# DISCRETE_OUT.net
KiCad netlist of a schematic drawn in Altium Designer
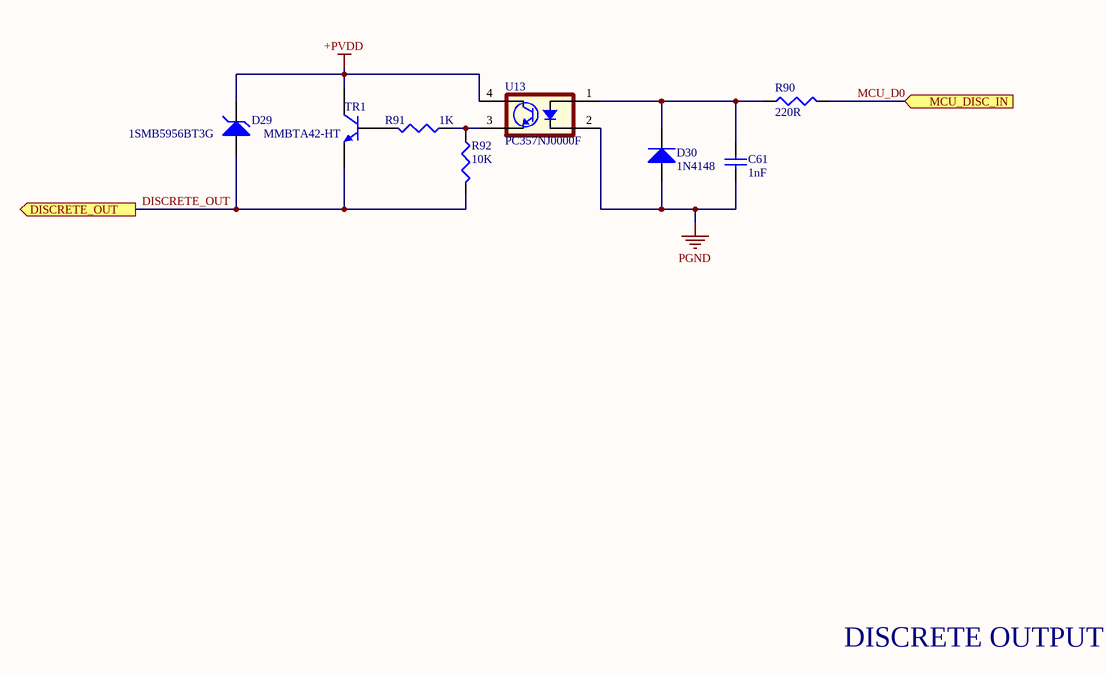
[diagram p0: DISCRETE_OUT.SchDoc]

(export (version "E")
  (design (tool "Eeschema 10.0.6"))
  (components
    (comp (ref "C61")
      (value "1nF")
      (footprint "C 0603(1608)x0.8_3")
      (description "Cap Ceramic 0.001uF 50V X7R 10% SMD 0603 125C Paper T/R")
      (fields
        (field (name "MANUFACTURER") "Murata")
        (field (name "MANUFACTURER PART NUMBER") "GCM188R71H102KA37D")
      )
      (libsource (lib "Miscellaneous Devices") (part "Cap"))
    )
    (comp (ref "D29")
      (value "1SMB5956BT3G")
      (footprint "DO214AA")
      (description "DIODE 1SMB5956BT3G ZENER 200V 3W DO214AA")
      (fields (field (name "MANUFACTURER") "ON SEMI"))
      (libsource (lib "DISCRETE_LIB") (part "DIODE 1SMB5956BT3G ZENER 200V 3W DO214AA"))
    )
    (comp (ref "D30")
      (value "1N4148")
      (footprint "SOD123")
      (description "DIODE 1N4148 GEN PURP 100V 150MA SOD123")
      (fields (field (name "MANUFACTURER") "MICRO COMMERCIAL"))
      (libsource (lib "DISCRETE_LIB") (part "DIODE 1N4148 GEN PURP 100V 150MA SOD123"))
    )
    (comp (ref "R90")
      (value "220R")
      (footprint "R 0603(1608)")
      (fields
        (field (name "MANUFACTURER") "Yageo")
        (field (name "MANUFACTURER PART NUMBER") "RC0603FR-07220RL")
        (field (name "TOLERANCE") "1%")
      )
      (libsource (lib "Miscellaneous Devices") (part "Res3"))
    )
    (comp (ref "R91")
      (value "1K")
      (footprint "R 0603(1608)")
      (description "RES SMD 1K OHM 1% 1/10W 0603")
      (fields
        (field (name "MANUFACTURER") "Yageo")
        (field (name "MANUFACTURER PART NUMBER") "RC0603FR-071KL")
      )
      (libsource (lib "Miscellaneous Devices") (part "Res3"))
    )
    (comp (ref "R92")
      (value "10K")
      (footprint "R 0603(1608)")
      (description "Res General Purpose Thick Film 0603 10K Ohm 1% 1/10W ±100ppm/°C Molded SMD Paper T/R")
      (fields
        (field (name "MANUFACTURER") "Yageo")
        (field (name "MANUFACTURER PART NUMBER") "RC0603FR-0710KL")
      )
      (libsource (lib "Miscellaneous Devices") (part "Res3"))
    )
    (comp (ref "TR1")
      (value "MMBTA42-HT")
      (footprint "SOT23-3")
      (description "TRANS MMBTA42-HT BIPOLAR TRANSISTOR NPN SOT23")
      (fields (field (name "MANUFACTURER") "HOTTECH"))
      (libsource (lib "DISCRETE_LIB") (part "MMBTA42-HT"))
    )
    (comp (ref "U13")
      (value "PC357NJ0000F")
      (footprint "SOIC_1TJ00F_SHP")
      (fields (field (name "MANUFACTURER") "Socle Technology"))
      (libsource (lib "opto") (part "PC357NJ0000F"))
    )
  )
  (nets
    (net (code "1") (name "+PVDD") (class "Default")
      (node (ref "D29") (pin "2") (pinfunction "K_2") (pintype "passive"))
      (node (ref "TR1") (pin "3") (pinfunction "C_3") (pintype "passive"))
      (node (ref "U13") (pin "4") (pinfunction "4_4") (pintype "passive"))
    )
    (net (code "2") (name "/DISCRETE_OUT") (class "Default")
      (node (ref "D29") (pin "1") (pinfunction "A_1") (pintype "passive"))
      (node (ref "R92") (pin "2") (pinfunction "2_2") (pintype "passive"))
      (node (ref "TR1") (pin "2") (pinfunction "E_2") (pintype "passive"))
    )
    (net (code "3") (name "/MCU_D0") (class "Default")
      (node (ref "R90") (pin "2") (pinfunction "2_2") (pintype "passive"))
    )
    (net (code "4") (name "Net-(D30-K)") (class "Default")
      (node (ref "C61") (pin "1") (pinfunction "1_1") (pintype "passive"))
      (node (ref "D30") (pin "2") (pinfunction "K_2") (pintype "passive"))
      (node (ref "R90") (pin "1") (pinfunction "1_1") (pintype "passive"))
      (node (ref "U13") (pin "1") (pinfunction "1_1") (pintype "passive"))
    )
    (net (code "5") (name "Net-(R91-Pad1)") (class "Default")
      (node (ref "R91") (pin "1") (pinfunction "1_1") (pintype "passive"))
      (node (ref "R92") (pin "1") (pinfunction "1_1") (pintype "passive"))
      (node (ref "U13") (pin "3") (pinfunction "3_3") (pintype "passive"))
    )
    (net (code "6") (name "Net-(TR1-B)") (class "Default")
      (node (ref "R91") (pin "2") (pinfunction "2_2") (pintype "passive"))
      (node (ref "TR1") (pin "1") (pinfunction "B_1") (pintype "passive"))
    )
    (net (code "7") (name "PGND") (class "Default")
      (node (ref "C61") (pin "2") (pinfunction "2_2") (pintype "passive"))
      (node (ref "D30") (pin "1") (pinfunction "A_1") (pintype "passive"))
      (node (ref "U13") (pin "2") (pinfunction "2_2") (pintype "passive"))
    )
  )
)
